# CleverBoard_V1.net
KiCad netlist of a schematic drawn in EAGLE
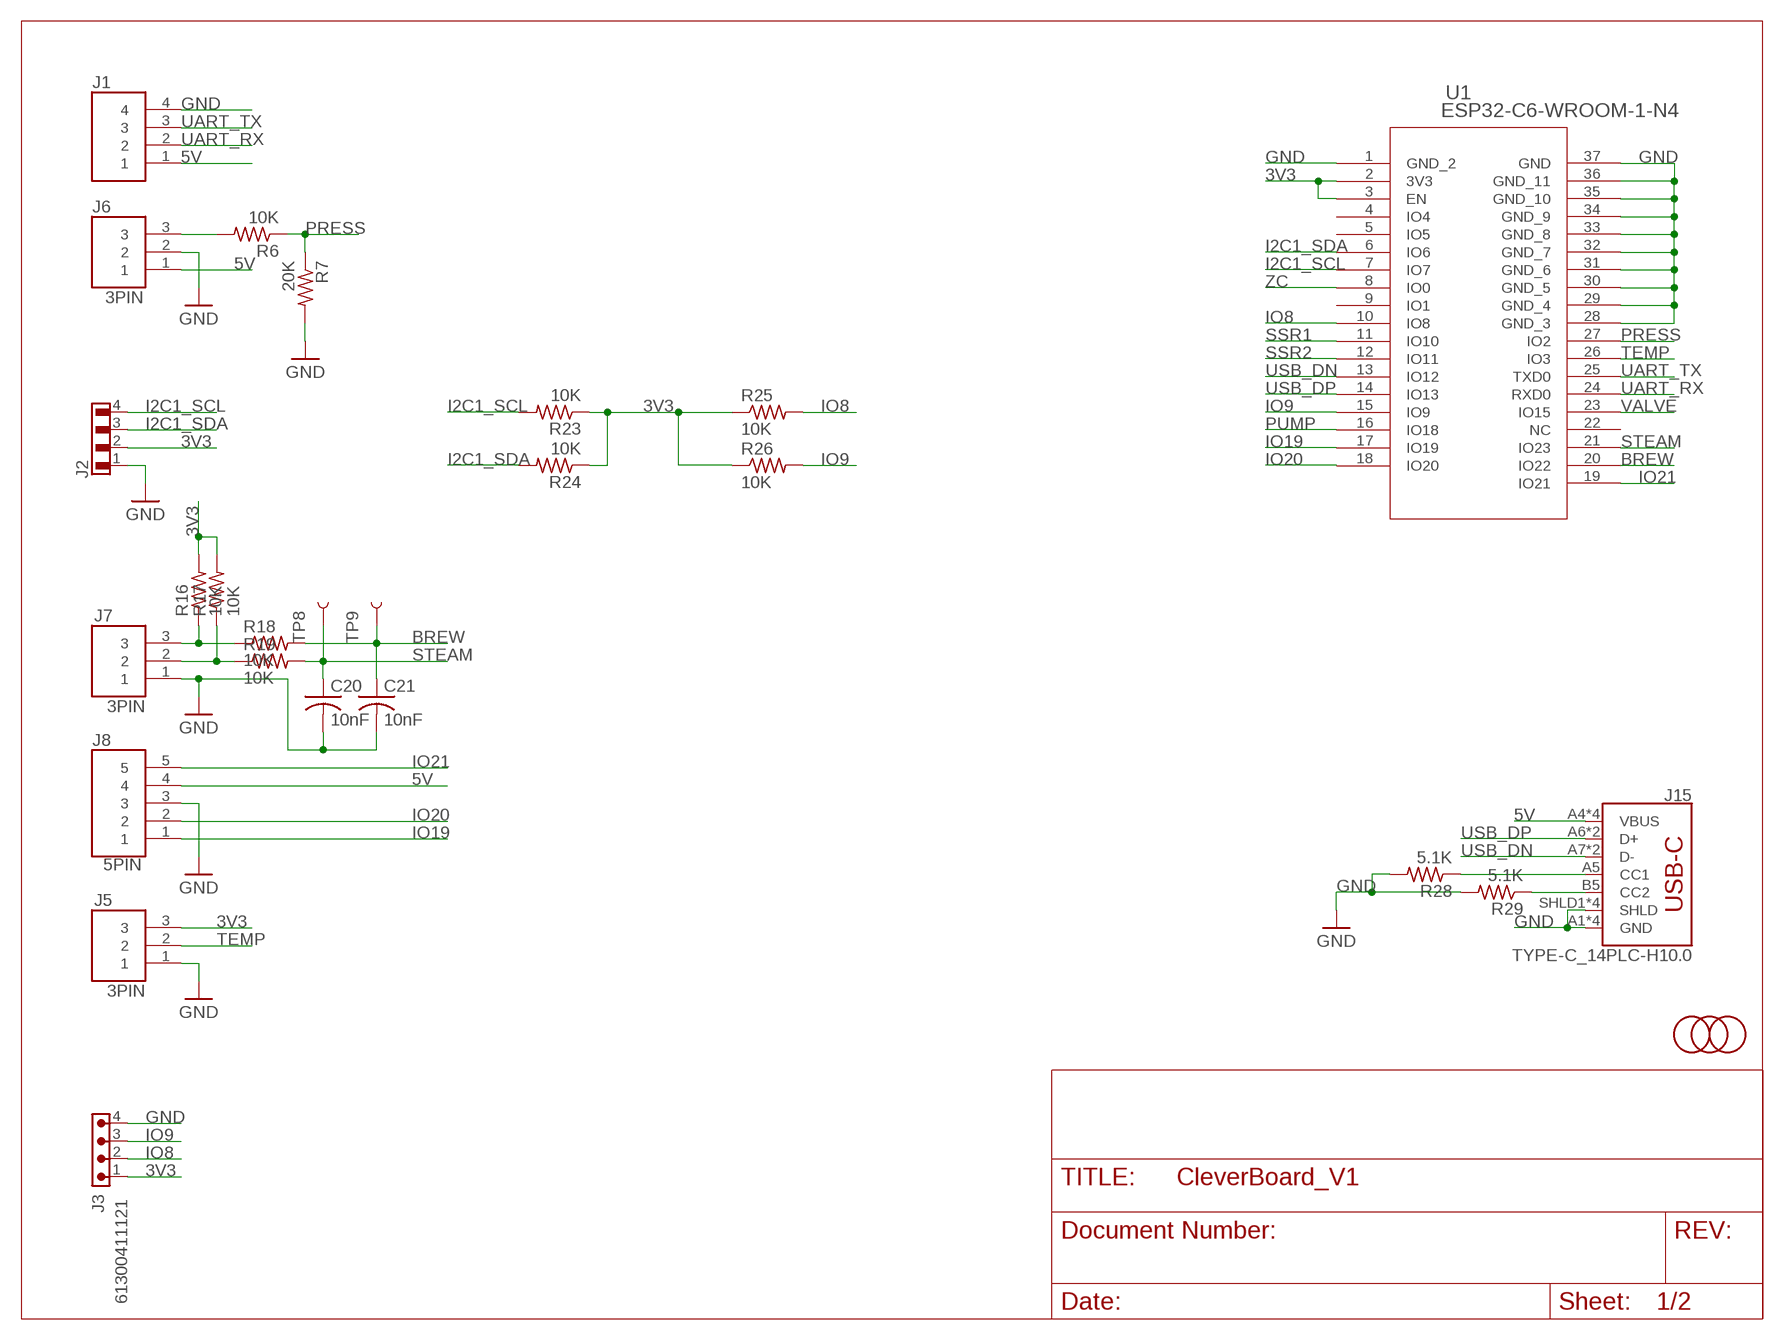
[diagram p0: schematic, sheet 1]
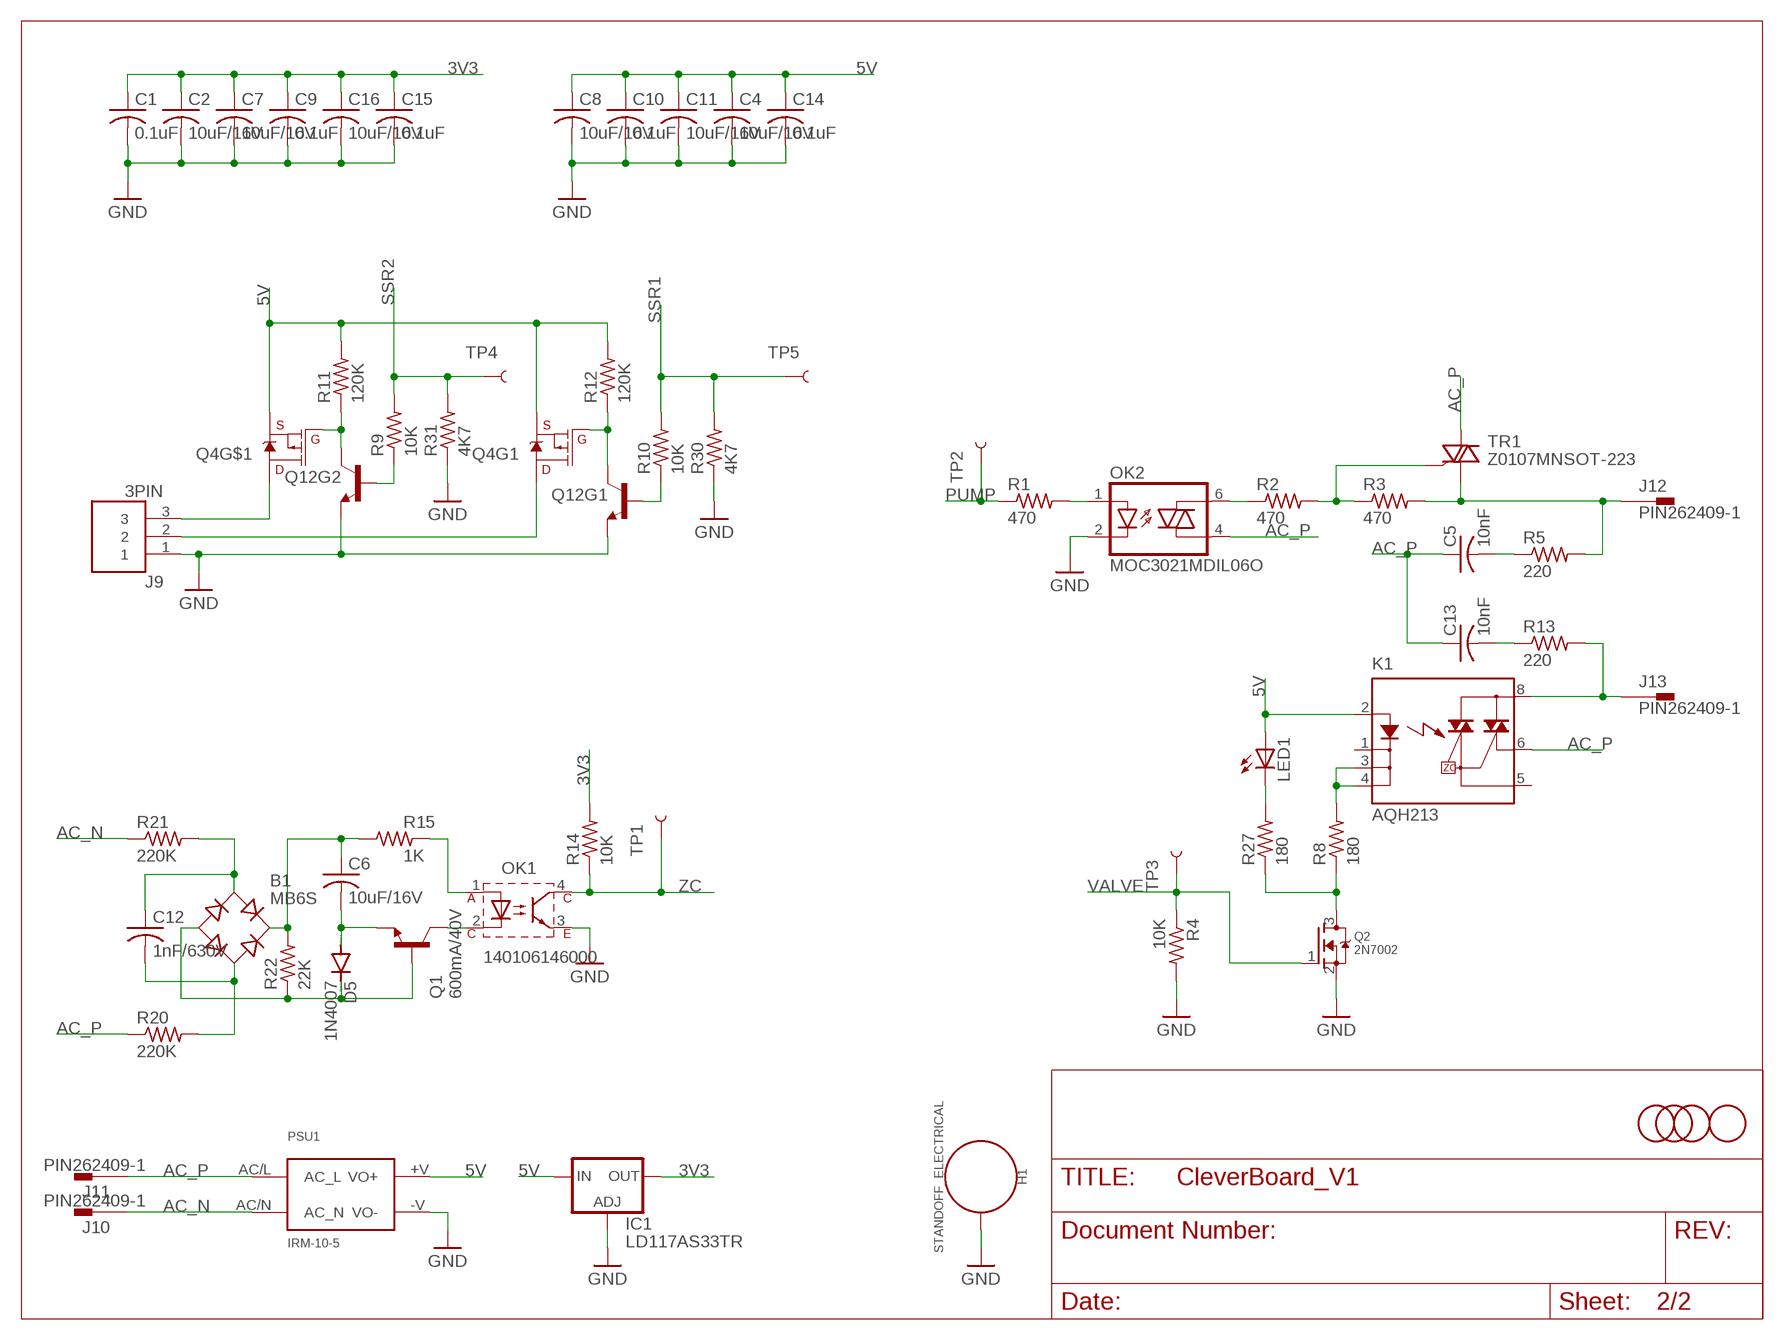
[diagram p1: schematic, sheet 2]

(export (version "E")
  (design (tool "Eeschema 10.0.6"))
  (components
    (comp (ref "C20")
      (value "10nF")
      (footprint "eagle-import:C0603")
      (libsource (lib "eagle-import") (part "C-USC0603"))
    )
    (comp (ref "C21")
      (value "10nF")
      (footprint "eagle-import:C0603")
      (libsource (lib "eagle-import") (part "C-USC0603"))
    )
    (comp (ref "J1")
      (value "4PIN")
      (footprint "eagle-import:B4B-PH-K-S")
      (libsource (lib "eagle-import") (part "4PIN"))
    )
    (comp (ref "J2")
      (value "665104131822")
      (footprint "eagle-import:665104131822")
      (libsource (lib "eagle-import") (part "665104131822"))
    )
    (comp (ref "J3")
      (value "61300411121")
      (footprint "eagle-import:61300411121")
      (libsource (lib "eagle-import") (part "6130XX11121_61300411121"))
    )
    (comp (ref "J5")
      (value "3PIN")
      (footprint "eagle-import:B3B-PH-K-S")
      (libsource (lib "eagle-import") (part "3PIN"))
    )
    (comp (ref "J6")
      (value "3PIN")
      (footprint "eagle-import:B3B-PH-K-S")
      (libsource (lib "eagle-import") (part "3PIN"))
    )
    (comp (ref "J7")
      (value "3PIN")
      (footprint "eagle-import:B3B-PH-K-S")
      (libsource (lib "eagle-import") (part "3PIN"))
    )
    (comp (ref "J8")
      (value "5PIN")
      (footprint "eagle-import:B5B-PH-K-S")
      (libsource (lib "eagle-import") (part "5PIN"))
    )
    (comp (ref "J15")
      (value "TYPE-C_14PLC-H10.0")
      (footprint "eagle-import:TYPE-C_14PLC-H10.0")
      (libsource (lib "eagle-import") (part "TYPE-C_14PLC-H10.0"))
    )
    (comp (ref "MARK1")
      (value "FIDUCIAL")
      (footprint "eagle-import:FIDUCIAL_1MM")
      (libsource (lib "eagle-import") (part "FIDUCIAL"))
    )
    (comp (ref "MARK2")
      (value "FIDUCIAL")
      (footprint "eagle-import:FIDUCIAL_1MM")
      (libsource (lib "eagle-import") (part "FIDUCIAL"))
    )
    (comp (ref "MARK5")
      (value "FIDUCIAL")
      (footprint "eagle-import:FIDUCIAL_1MM")
      (libsource (lib "eagle-import") (part "FIDUCIAL"))
    )
    (comp (ref "R6")
      (value "10K")
      (footprint "eagle-import:R0603")
      (libsource (lib "eagle-import") (part "R-US_R0603"))
    )
    (comp (ref "R7")
      (value "20K")
      (footprint "eagle-import:R0603")
      (libsource (lib "eagle-import") (part "R-US_R0603"))
    )
    (comp (ref "R16")
      (value "10K")
      (footprint "eagle-import:R0603")
      (libsource (lib "eagle-import") (part "R-US_R0603"))
    )
    (comp (ref "R17")
      (value "10K")
      (footprint "eagle-import:R0603")
      (libsource (lib "eagle-import") (part "R-US_R0603"))
    )
    (comp (ref "R18")
      (value "10K")
      (footprint "eagle-import:R0603")
      (libsource (lib "eagle-import") (part "R-US_R0603"))
    )
    (comp (ref "R19")
      (value "10K")
      (footprint "eagle-import:R0603")
      (libsource (lib "eagle-import") (part "R-US_R0603"))
    )
    (comp (ref "R23")
      (value "10K")
      (footprint "eagle-import:R0603")
      (libsource (lib "eagle-import") (part "R-US_R0603"))
    )
    (comp (ref "R24")
      (value "10K")
      (footprint "eagle-import:R0603")
      (libsource (lib "eagle-import") (part "R-US_R0603"))
    )
    (comp (ref "R25")
      (value "10K")
      (footprint "eagle-import:R0603")
      (libsource (lib "eagle-import") (part "R-US_R0603"))
    )
    (comp (ref "R26")
      (value "10K")
      (footprint "eagle-import:R0603")
      (libsource (lib "eagle-import") (part "R-US_R0603"))
    )
    (comp (ref "R28")
      (value "5.1K")
      (footprint "eagle-import:R0603")
      (libsource (lib "eagle-import") (part "R-US_R0603"))
    )
    (comp (ref "R29")
      (value "5.1K")
      (footprint "eagle-import:R0603")
      (libsource (lib "eagle-import") (part "R-US_R0603"))
    )
    (comp (ref "TP8")
      (value "TEST-POINT3")
      (footprint "eagle-import:PAD.03X.03")
      (libsource (lib "eagle-import") (part "TEST-POINT3"))
    )
    (comp (ref "TP9")
      (value "TEST-POINT3")
      (footprint "eagle-import:PAD.03X.03")
      (libsource (lib "eagle-import") (part "TEST-POINT3"))
    )
    (comp (ref "U1")
      (value "ESP32-C6-WROOM-1-N4")
      (footprint "eagle-import:MOD28_ESP32-C6-WROOM-1_EXP")
      (fields (field (name "COPYRIGHT") "Copyright (C) 2025 Ultra Librarian. All rights reserved."))
      (libsource (lib "eagle-import") (part "ESP32-C6-WROOM-1-N4"))
    )
    (comp (ref "B1")
      (value "MB6S")
      (footprint "eagle-import:SOIC-4")
      (libsource (lib "eagle-import") (part "MBS6"))
    )
    (comp (ref "C1")
      (value "0.1uF")
      (footprint "eagle-import:C0603")
      (libsource (lib "eagle-import") (part "C-USC0603"))
    )
    (comp (ref "C2")
      (value "10uF/16V")
      (footprint "eagle-import:C0603")
      (libsource (lib "eagle-import") (part "C-USC0603"))
    )
    (comp (ref "C4")
      (value "10uF/16V")
      (footprint "eagle-import:C0603")
      (libsource (lib "eagle-import") (part "C-USC0603"))
    )
    (comp (ref "C5")
      (value "10nF")
      (footprint "eagle-import:C1206")
      (libsource (lib "eagle-import") (part "C-USC1206"))
    )
    (comp (ref "C6")
      (value "10uF/16V")
      (footprint "eagle-import:C0603")
      (libsource (lib "eagle-import") (part "C-USC0603"))
    )
    (comp (ref "C7")
      (value "10uF/16V")
      (footprint "eagle-import:C0603")
      (libsource (lib "eagle-import") (part "C-USC0603"))
    )
    (comp (ref "C8")
      (value "10uF/16V")
      (footprint "eagle-import:C0603")
      (libsource (lib "eagle-import") (part "C-USC0603"))
    )
    (comp (ref "C9")
      (value "0.1uF")
      (footprint "eagle-import:C0603")
      (libsource (lib "eagle-import") (part "C-USC0603"))
    )
    (comp (ref "C10")
      (value "0.1uF")
      (footprint "eagle-import:C0603")
      (libsource (lib "eagle-import") (part "C-USC0603"))
    )
    (comp (ref "C11")
      (value "10uF/16V")
      (footprint "eagle-import:C0603")
      (libsource (lib "eagle-import") (part "C-USC0603"))
    )
    (comp (ref "C12")
      (value "1nF/630V")
      (footprint "eagle-import:C0805")
      (libsource (lib "eagle-import") (part "C-USC0805"))
    )
    (comp (ref "C13")
      (value "10nF")
      (footprint "eagle-import:C1206")
      (libsource (lib "eagle-import") (part "C-USC1206"))
    )
    (comp (ref "C14")
      (value "0.1uF")
      (footprint "eagle-import:C0603")
      (libsource (lib "eagle-import") (part "C-USC0603"))
    )
    (comp (ref "C15")
      (value "0.1uF")
      (footprint "eagle-import:C0603")
      (libsource (lib "eagle-import") (part "C-USC0603"))
    )
    (comp (ref "C16")
      (value "10uF/16V")
      (footprint "eagle-import:C0603")
      (libsource (lib "eagle-import") (part "C-USC0603"))
    )
    (comp (ref "D5")
      (value "1N4007")
      (footprint "eagle-import:DO214AC")
      (libsource (lib "eagle-import") (part "DIODE-DO214AC"))
    )
    (comp (ref "H1")
      (value "STANDOFF_ELECTRICAL")
      (footprint "eagle-import:STANDOFF-ELECTRICAL")
      (libsource (lib "eagle-import") (part "STANDOFF_ELECTRICAL"))
    )
    (comp (ref "IC1")
      (value "LD117AS33TR")
      (footprint "eagle-import:SOT223")
      (libsource (lib "eagle-import") (part "LD117A?S33TR"))
    )
    (comp (ref "J9")
      (value "3PIN")
      (footprint "eagle-import:B3B-PH-K-S")
      (libsource (lib "eagle-import") (part "3PIN"))
    )
    (comp (ref "J10")
      (value "PIN262409-1")
      (footprint "eagle-import:62409-1")
      (libsource (lib "eagle-import") (part "PIN262409-1"))
    )
    (comp (ref "J11")
      (value "PIN262409-1")
      (footprint "eagle-import:62409-1")
      (libsource (lib "eagle-import") (part "PIN262409-1"))
    )
    (comp (ref "J12")
      (value "PIN262409-1")
      (footprint "eagle-import:62409-1")
      (libsource (lib "eagle-import") (part "PIN262409-1"))
    )
    (comp (ref "J13")
      (value "PIN262409-1")
      (footprint "eagle-import:62409-1")
      (libsource (lib "eagle-import") (part "PIN262409-1"))
    )
    (comp (ref "K1")
      (value "AQH213")
      (footprint "eagle-import:DIL07")
      (libsource (lib "eagle-import") (part "AQH213"))
    )
    (comp (ref "LED1")
      (value "LEDCHIP-LED0603")
      (footprint "eagle-import:CHIP-LED0603")
      (libsource (lib "eagle-import") (part "LEDCHIP-LED0603"))
    )
    (comp (ref "MARK4")
      (value "FIDUCIAL")
      (footprint "eagle-import:FIDUCIAL_1MM")
      (libsource (lib "eagle-import") (part "FIDUCIAL"))
    )
    (comp (ref "MARK6")
      (value "FIDUCIAL")
      (footprint "eagle-import:FIDUCIAL_1MM")
      (libsource (lib "eagle-import") (part "FIDUCIAL"))
    )
    (comp (ref "MARK7")
      (value "FIDUCIAL")
      (footprint "eagle-import:FIDUCIAL_1MM")
      (libsource (lib "eagle-import") (part "FIDUCIAL"))
    )
    (comp (ref "MARK8")
      (value "FIDUCIAL")
      (footprint "eagle-import:FIDUCIAL_1MM")
      (libsource (lib "eagle-import") (part "FIDUCIAL"))
    )
    (comp (ref "OK1")
      (value "140106146000")
      (footprint "eagle-import:WL-OCPT_LSOP4")
      (libsource (lib "eagle-import") (part "WL-OCPT_SERIES_101X_140106146000"))
    )
    (comp (ref "OK2")
      (value "MOC3021MDIL06O")
      (footprint "eagle-import:DIL06O")
      (libsource (lib "eagle-import") (part "MOC3021MDIL06O"))
    )
    (comp (ref "PSU1")
      (value "IRM-10-5")
      (footprint "eagle-import:IRM-10")
      (fields (field (name "SPICEPREFIX") "E"))
      (libsource (lib "eagle-import") (part "IRM-10-5"))
    )
    (comp (ref "Q1")
      (value "600mA/40V")
      (footprint "eagle-import:SOT23-3")
      (libsource (lib "eagle-import") (part "TRANS_NPN-MMBT2222AL"))
    )
    (comp (ref "Q2")
      (value "2N7002")
      (footprint "eagle-import:SOT23-R")
      (libsource (lib "eagle-import") (part "MOSFET-NREFLOW"))
    )
    (comp (ref "Q4")
      (value "MOSFET_PCH_DUAL-DMP2240UDM")
      (footprint "eagle-import:SOT26")
      (fields (field (name "LCSC") "C397948"))
      (libsource (lib "eagle-import") (part "MOSFET_PCH_DUAL-DMP2240UDM"))
    )
    (comp (ref "Q12")
      (value "TRANS_NPN_DUAL-MBT3904DW1T1")
      (footprint "eagle-import:SC70-6")
      (fields (field (name "LCSC") "C896759"))
      (libsource (lib "eagle-import") (part "TRANS_NPN_DUAL-MBT3904DW1T1"))
    )
    (comp (ref "R1")
      (value "470")
      (footprint "eagle-import:R0603")
      (libsource (lib "eagle-import") (part "R-US_R0603"))
    )
    (comp (ref "R2")
      (value "470")
      (footprint "eagle-import:R0603")
      (libsource (lib "eagle-import") (part "R-US_R0603"))
    )
    (comp (ref "R3")
      (value "470")
      (footprint "eagle-import:R0603")
      (libsource (lib "eagle-import") (part "R-US_R0603"))
    )
    (comp (ref "R4")
      (value "10K")
      (footprint "eagle-import:R0603")
      (libsource (lib "eagle-import") (part "R-US_R0603"))
    )
    (comp (ref "R5")
      (value "220")
      (footprint "eagle-import:R2512")
      (libsource (lib "eagle-import") (part "R-US_R2512"))
    )
    (comp (ref "R8")
      (value "180")
      (footprint "eagle-import:R0603")
      (libsource (lib "eagle-import") (part "R-US_R0603"))
    )
    (comp (ref "R9")
      (value "10K")
      (footprint "eagle-import:R0603")
      (libsource (lib "eagle-import") (part "R-US_R0603"))
    )
    (comp (ref "R10")
      (value "10K")
      (footprint "eagle-import:R0603")
      (libsource (lib "eagle-import") (part "R-US_R0603"))
    )
    (comp (ref "R11")
      (value "120K")
      (footprint "eagle-import:R0603")
      (libsource (lib "eagle-import") (part "R-US_R0603"))
    )
    (comp (ref "R12")
      (value "120K")
      (footprint "eagle-import:R0603")
      (libsource (lib "eagle-import") (part "R-US_R0603"))
    )
    (comp (ref "R13")
      (value "220")
      (footprint "eagle-import:R2512")
      (libsource (lib "eagle-import") (part "R-US_R2512"))
    )
    (comp (ref "R14")
      (value "10K")
      (footprint "eagle-import:R0603")
      (libsource (lib "eagle-import") (part "R-US_R0603"))
    )
    (comp (ref "R15")
      (value "1K")
      (footprint "eagle-import:R0603")
      (libsource (lib "eagle-import") (part "R-US_R0603"))
    )
    (comp (ref "R20")
      (value "220K")
      (footprint "eagle-import:R1206")
      (libsource (lib "eagle-import") (part "R-US_R1206"))
    )
    (comp (ref "R21")
      (value "220K")
      (footprint "eagle-import:R1206")
      (libsource (lib "eagle-import") (part "R-US_R1206"))
    )
    (comp (ref "R22")
      (value "22K")
      (footprint "eagle-import:R0603")
      (libsource (lib "eagle-import") (part "R-US_R0603"))
    )
    (comp (ref "R27")
      (value "180")
      (footprint "eagle-import:R0603")
      (libsource (lib "eagle-import") (part "R-US_R0603"))
    )
    (comp (ref "R30")
      (value "4K7")
      (footprint "eagle-import:R0603")
      (libsource (lib "eagle-import") (part "R-US_R0603"))
    )
    (comp (ref "R31")
      (value "4K7")
      (footprint "eagle-import:R0603")
      (libsource (lib "eagle-import") (part "R-US_R0603"))
    )
    (comp (ref "TP1")
      (value "TEST-POINT3")
      (footprint "eagle-import:PAD.03X.03")
      (libsource (lib "eagle-import") (part "TEST-POINT3"))
    )
    (comp (ref "TP2")
      (value "TEST-POINT3")
      (footprint "eagle-import:PAD.03X.03")
      (libsource (lib "eagle-import") (part "TEST-POINT3"))
    )
    (comp (ref "TP3")
      (value "TEST-POINT3")
      (footprint "eagle-import:PAD.03X.03")
      (libsource (lib "eagle-import") (part "TEST-POINT3"))
    )
    (comp (ref "TP4")
      (value "TEST-POINT3")
      (footprint "eagle-import:PAD.03X.03")
      (libsource (lib "eagle-import") (part "TEST-POINT3"))
    )
    (comp (ref "TP5")
      (value "TEST-POINT3")
      (footprint "eagle-import:PAD.03X.03")
      (libsource (lib "eagle-import") (part "TEST-POINT3"))
    )
    (comp (ref "TR1")
      (value "Z0107MNSOT-223")
      (footprint "eagle-import:SOT223")
      (libsource (lib "eagle-import") (part "Z0107MNSOT-223"))
    )
  )
  (nets
    (net (code "1") (name "3V3") (class "Default")
      (node (ref "C1") (pin "1") (pinfunction "1_1") (pintype "passive"))
      (node (ref "C15") (pin "1") (pinfunction "1_1") (pintype "passive"))
      (node (ref "C16") (pin "1") (pinfunction "1_1") (pintype "passive"))
      (node (ref "C2") (pin "1") (pinfunction "1_1") (pintype "passive"))
      (node (ref "C7") (pin "1") (pinfunction "1_1") (pintype "passive"))
      (node (ref "C9") (pin "1") (pinfunction "1_1") (pintype "passive"))
      (node (ref "IC1") (pin "4") (pinfunction "OUT_4") (pintype "passive"))
      (node (ref "J2") (pin "2") (pinfunction "2_2") (pintype "passive"))
      (node (ref "J3") (pin "1") (pinfunction "1_1") (pintype "passive"))
      (node (ref "J5") (pin "3") (pinfunction "3_3") (pintype "bidirectional"))
      (node (ref "R14") (pin "2") (pinfunction "2_2") (pintype "passive"))
      (node (ref "R16") (pin "2") (pinfunction "2_2") (pintype "passive"))
      (node (ref "R17") (pin "2") (pinfunction "2_2") (pintype "passive"))
      (node (ref "R23") (pin "1") (pinfunction "1_1") (pintype "passive"))
      (node (ref "R24") (pin "1") (pinfunction "1_1") (pintype "passive"))
      (node (ref "R25") (pin "1") (pinfunction "1_1") (pintype "passive"))
      (node (ref "R26") (pin "1") (pinfunction "1_1") (pintype "passive"))
      (node (ref "U1") (pin "2") (pinfunction "3V3_2") (pintype "power_in"))
      (node (ref "U1") (pin "3") (pinfunction "EN_3") (pintype "input"))
    )
    (net (code "2") (name "5V") (class "Default")
      (node (ref "C10") (pin "1") (pinfunction "1_1") (pintype "passive"))
      (node (ref "C11") (pin "1") (pinfunction "1_1") (pintype "passive"))
      (node (ref "C14") (pin "1") (pinfunction "1_1") (pintype "passive"))
      (node (ref "C4") (pin "1") (pinfunction "1_1") (pintype "passive"))
      (node (ref "C8") (pin "1") (pinfunction "1_1") (pintype "passive"))
      (node (ref "IC1") (pin "3") (pinfunction "IN_3") (pintype "input"))
      (node (ref "J1") (pin "1") (pinfunction "1_1") (pintype "bidirectional"))
      (node (ref "J15") (pin "A4") (pinfunction "VBUS_A4") (pintype "bidirectional"))
      (node (ref "J15") (pin "A9") (pinfunction "VBUS_A9") (pintype "bidirectional"))
      (node (ref "J15") (pin "B4") (pinfunction "VBUS_B4") (pintype "bidirectional"))
      (node (ref "J15") (pin "B9") (pinfunction "VBUS_B9") (pintype "bidirectional"))
      (node (ref "J6") (pin "1") (pinfunction "1_1") (pintype "bidirectional"))
      (node (ref "J8") (pin "4") (pinfunction "4_4") (pintype "bidirectional"))
      (node (ref "K1") (pin "2") (pinfunction "A_2") (pintype "passive"))
      (node (ref "LED1") (pin "A") (pinfunction "A_A") (pintype "passive"))
      (node (ref "PSU1") (pin "+V") (pinfunction "VO+_+V") (pintype "bidirectional"))
      (node (ref "Q4") (pin "S1") (pinfunction "S_S1") (pintype "bidirectional"))
      (node (ref "Q4") (pin "S2") (pinfunction "S_S2") (pintype "bidirectional"))
      (node (ref "R11") (pin "2") (pinfunction "2_2") (pintype "passive"))
      (node (ref "R12") (pin "2") (pinfunction "2_2") (pintype "passive"))
    )
    (net (code "3") (name "AC_N") (class "Default")
      (node (ref "J10") (pin "A1") (pinfunction "1_A1") (pintype "passive"))
      (node (ref "J10") (pin "A2") (pinfunction "1_A2") (pintype "passive"))
      (node (ref "PSU1") (pin "AC/N") (pinfunction "AC_N_AC/N") (pintype "bidirectional"))
      (node (ref "R21") (pin "1") (pinfunction "1_1") (pintype "passive"))
    )
    (net (code "4") (name "AC_P") (class "Default")
      (node (ref "C13") (pin "1") (pinfunction "1_1") (pintype "passive"))
      (node (ref "C5") (pin "1") (pinfunction "1_1") (pintype "passive"))
      (node (ref "J11") (pin "A1") (pinfunction "1_A1") (pintype "passive"))
      (node (ref "J11") (pin "A2") (pinfunction "1_A2") (pintype "passive"))
      (node (ref "K1") (pin "6") (pinfunction "DS3_6") (pintype "passive"))
      (node (ref "OK2") (pin "4") (pinfunction "A1_4") (pintype "passive"))
      (node (ref "PSU1") (pin "AC/L") (pinfunction "AC_L_AC/L") (pintype "bidirectional"))
      (node (ref "R20") (pin "1") (pinfunction "1_1") (pintype "passive"))
      (node (ref "TR1") (pin "2") (pinfunction "A2_2") (pintype "passive"))
      (node (ref "TR1") (pin "4") (pinfunction "A2_4") (pintype "passive"))
    )
    (net (code "5") (name "BREW") (class "Default")
      (node (ref "C21") (pin "1") (pinfunction "1_1") (pintype "passive"))
      (node (ref "R18") (pin "2") (pinfunction "2_2") (pintype "passive"))
      (node (ref "TP9") (pin "1") (pinfunction "1_1") (pintype "bidirectional"))
      (node (ref "U1") (pin "20") (pinfunction "IO22_20") (pintype "bidirectional"))
    )
    (net (code "6") (name "GND") (class "Default")
      (node (ref "C1") (pin "2") (pinfunction "2_2") (pintype "passive"))
      (node (ref "C10") (pin "2") (pinfunction "2_2") (pintype "passive"))
      (node (ref "C11") (pin "2") (pinfunction "2_2") (pintype "passive"))
      (node (ref "C14") (pin "2") (pinfunction "2_2") (pintype "passive"))
      (node (ref "C15") (pin "2") (pinfunction "2_2") (pintype "passive"))
      (node (ref "C16") (pin "2") (pinfunction "2_2") (pintype "passive"))
      (node (ref "C2") (pin "2") (pinfunction "2_2") (pintype "passive"))
      (node (ref "C20") (pin "2") (pinfunction "2_2") (pintype "passive"))
      (node (ref "C21") (pin "2") (pinfunction "2_2") (pintype "passive"))
      (node (ref "C4") (pin "2") (pinfunction "2_2") (pintype "passive"))
      (node (ref "C7") (pin "2") (pinfunction "2_2") (pintype "passive"))
      (node (ref "C8") (pin "2") (pinfunction "2_2") (pintype "passive"))
      (node (ref "C9") (pin "2") (pinfunction "2_2") (pintype "passive"))
      (node (ref "H1") (pin "P1") (pinfunction "P$1_P1") (pintype "bidirectional"))
      (node (ref "IC1") (pin "1") (pinfunction "ADJ_1") (pintype "input"))
      (node (ref "J1") (pin "4") (pinfunction "4_4") (pintype "bidirectional"))
      (node (ref "J15") (pin "A1") (pinfunction "GND_A1") (pintype "bidirectional"))
      (node (ref "J15") (pin "A12") (pinfunction "GND_A12") (pintype "bidirectional"))
      (node (ref "J15") (pin "B1") (pinfunction "GND_B1") (pintype "bidirectional"))
      (node (ref "J15") (pin "B12") (pinfunction "GND_B12") (pintype "bidirectional"))
      (node (ref "J15") (pin "SHLD1") (pinfunction "SHLD_SHLD1") (pintype "bidirectional"))
      (node (ref "J15") (pin "SHLD2") (pinfunction "SHLD_SHLD2") (pintype "bidirectional"))
      (node (ref "J15") (pin "SHLD3") (pinfunction "SHLD_SHLD3") (pintype "bidirectional"))
      (node (ref "J15") (pin "SHLD4") (pinfunction "SHLD_SHLD4") (pintype "bidirectional"))
      (node (ref "J2") (pin "1") (pinfunction "1_1") (pintype "passive"))
      (node (ref "J3") (pin "4") (pinfunction "4_4") (pintype "passive"))
      (node (ref "J5") (pin "1") (pinfunction "1_1") (pintype "bidirectional"))
      (node (ref "J6") (pin "2") (pinfunction "2_2") (pintype "bidirectional"))
      (node (ref "J7") (pin "1") (pinfunction "1_1") (pintype "bidirectional"))
      (node (ref "J8") (pin "3") (pinfunction "3_3") (pintype "bidirectional"))
      (node (ref "J9") (pin "1") (pinfunction "1_1") (pintype "bidirectional"))
      (node (ref "OK1") (pin "3") (pinfunction "3_3") (pintype "passive"))
      (node (ref "OK2") (pin "2") (pinfunction "C_2") (pintype "passive"))
      (node (ref "PSU1") (pin "-V") (pinfunction "VO-_-V") (pintype "bidirectional"))
      (node (ref "Q12") (pin "1") (pinfunction "E_1") (pintype "passive"))
      (node (ref "Q12") (pin "4") (pinfunction "E_4") (pintype "passive"))
      (node (ref "Q2") (pin "2") (pinfunction "S_2") (pintype "bidirectional"))
      (node (ref "R28") (pin "2") (pinfunction "2_2") (pintype "passive"))
      (node (ref "R29") (pin "2") (pinfunction "2_2") (pintype "passive"))
      (node (ref "R30") (pin "1") (pinfunction "1_1") (pintype "passive"))
      (node (ref "R31") (pin "1") (pinfunction "1_1") (pintype "passive"))
      (node (ref "R4") (pin "2") (pinfunction "2_2") (pintype "passive"))
      (node (ref "R7") (pin "2") (pinfunction "2_2") (pintype "passive"))
      (node (ref "U1") (pin "1") (pinfunction "GND_2_1") (pintype "passive"))
      (node (ref "U1") (pin "28") (pinfunction "GND_3_28") (pintype "passive"))
      (node (ref "U1") (pin "29") (pinfunction "GND_4_29") (pintype "passive"))
      (node (ref "U1") (pin "30") (pinfunction "GND_5_30") (pintype "passive"))
      (node (ref "U1") (pin "31") (pinfunction "GND_6_31") (pintype "passive"))
      (node (ref "U1") (pin "32") (pinfunction "GND_7_32") (pintype "passive"))
      (node (ref "U1") (pin "33") (pinfunction "GND_8_33") (pintype "passive"))
      (node (ref "U1") (pin "34") (pinfunction "GND_9_34") (pintype "passive"))
      (node (ref "U1") (pin "35") (pinfunction "GND_10_35") (pintype "passive"))
      (node (ref "U1") (pin "36") (pinfunction "GND_11_36") (pintype "passive"))
      (node (ref "U1") (pin "37") (pinfunction "GND_37") (pintype "passive"))
    )
    (net (code "7") (name "I2C1_SCL") (class "Default")
      (node (ref "J2") (pin "4") (pinfunction "4_4") (pintype "passive"))
      (node (ref "R23") (pin "2") (pinfunction "2_2") (pintype "passive"))
      (node (ref "U1") (pin "7") (pinfunction "IO7_7") (pintype "bidirectional"))
    )
    (net (code "8") (name "I2C1_SDA") (class "Default")
      (node (ref "J2") (pin "3") (pinfunction "3_3") (pintype "passive"))
      (node (ref "R24") (pin "2") (pinfunction "2_2") (pintype "passive"))
      (node (ref "U1") (pin "6") (pinfunction "IO6_6") (pintype "bidirectional"))
    )
    (net (code "9") (name "IO8") (class "Default")
      (node (ref "J3") (pin "2") (pinfunction "2_2") (pintype "passive"))
      (node (ref "R25") (pin "2") (pinfunction "2_2") (pintype "passive"))
      (node (ref "U1") (pin "10") (pinfunction "IO8_10") (pintype "bidirectional"))
    )
    (net (code "10") (name "IO9") (class "Default")
      (node (ref "J3") (pin "3") (pinfunction "3_3") (pintype "passive"))
      (node (ref "R26") (pin "2") (pinfunction "2_2") (pintype "passive"))
      (node (ref "U1") (pin "15") (pinfunction "IO9_15") (pintype "bidirectional"))
    )
    (net (code "11") (name "IO19") (class "Default")
      (node (ref "J8") (pin "1") (pinfunction "1_1") (pintype "bidirectional"))
      (node (ref "U1") (pin "17") (pinfunction "IO19_17") (pintype "bidirectional"))
    )
    (net (code "12") (name "IO20") (class "Default")
      (node (ref "J8") (pin "2") (pinfunction "2_2") (pintype "bidirectional"))
      (node (ref "U1") (pin "18") (pinfunction "IO20_18") (pintype "bidirectional"))
    )
    (net (code "13") (name "IO21") (class "Default")
      (node (ref "J8") (pin "5") (pinfunction "5_5") (pintype "bidirectional"))
      (node (ref "U1") (pin "19") (pinfunction "IO21_19") (pintype "bidirectional"))
    )
    (net (code "14") (name "Net-(B1-AC1)") (class "Default")
      (node (ref "B1") (pin "~1") (pinfunction "AC1_~1") (pintype "passive"))
      (node (ref "C12") (pin "2") (pinfunction "2_2") (pintype "passive"))
      (node (ref "R20") (pin "2") (pinfunction "2_2") (pintype "passive"))
    )
    (net (code "15") (name "Net-(B1-AC2)") (class "Default")
      (node (ref "B1") (pin "~2") (pinfunction "AC2_~2") (pintype "passive"))
      (node (ref "C12") (pin "1") (pinfunction "1_1") (pintype "passive"))
      (node (ref "R21") (pin "2") (pinfunction "2_2") (pintype "passive"))
    )
    (net (code "16") (name "Net-(B1-Pad+)") (class "Default")
      (node (ref "B1") (pin "+") (pinfunction "+_+") (pintype "passive"))
      (node (ref "C6") (pin "1") (pinfunction "1_1") (pintype "passive"))
      (node (ref "R15") (pin "1") (pinfunction "1_1") (pintype "passive"))
      (node (ref "R22") (pin "2") (pinfunction "2_2") (pintype "passive"))
    )
    (net (code "17") (name "Net-(C5-Pad2)") (class "Default")
      (node (ref "C5") (pin "2") (pinfunction "2_2") (pintype "passive"))
      (node (ref "R5") (pin "1") (pinfunction "1_1") (pintype "passive"))
    )
    (net (code "18") (name "Net-(C13-Pad2)") (class "Default")
      (node (ref "C13") (pin "2") (pinfunction "2_2") (pintype "passive"))
      (node (ref "R13") (pin "1") (pinfunction "1_1") (pintype "passive"))
    )
    (net (code "19") (name "Net-(J6-Pad3)") (class "Default")
      (node (ref "J6") (pin "3") (pinfunction "3_3") (pintype "bidirectional"))
      (node (ref "R6") (pin "2") (pinfunction "2_2") (pintype "passive"))
    )
    (net (code "20") (name "Net-(J7-Pad2)") (class "Default")
      (node (ref "J7") (pin "2") (pinfunction "2_2") (pintype "bidirectional"))
      (node (ref "R17") (pin "1") (pinfunction "1_1") (pintype "passive"))
      (node (ref "R19") (pin "1") (pinfunction "1_1") (pintype "passive"))
    )
    (net (code "21") (name "Net-(J7-Pad3)") (class "Default")
      (node (ref "J7") (pin "3") (pinfunction "3_3") (pintype "bidirectional"))
      (node (ref "R16") (pin "1") (pinfunction "1_1") (pintype "passive"))
      (node (ref "R18") (pin "1") (pinfunction "1_1") (pintype "passive"))
    )
    (net (code "22") (name "Net-(J15-CC1)") (class "Default")
      (node (ref "J15") (pin "A5") (pinfunction "CC1_A5") (pintype "bidirectional"))
      (node (ref "R28") (pin "1") (pinfunction "1_1") (pintype "passive"))
    )
    (net (code "23") (name "Net-(J15-CC2)") (class "Default")
      (node (ref "J15") (pin "B5") (pinfunction "CC2_B5") (pintype "bidirectional"))
      (node (ref "R29") (pin "1") (pinfunction "1_1") (pintype "passive"))
    )
    (net (code "24") (name "Net-(K1-DS1)") (class "Default")
      (node (ref "J13") (pin "A1") (pinfunction "1_A1") (pintype "passive"))
      (node (ref "J13") (pin "A2") (pinfunction "1_A2") (pintype "passive"))
      (node (ref "K1") (pin "8") (pinfunction "DS1_8") (pintype "passive"))
      (node (ref "R13") (pin "2") (pinfunction "2_2") (pintype "passive"))
    )
    (net (code "25") (name "Net-(K1-K1)") (class "Default")
      (node (ref "K1") (pin "3") (pinfunction "K1_3") (pintype "passive"))
      (node (ref "K1") (pin "4") (pinfunction "K2_4") (pintype "passive"))
      (node (ref "R8") (pin "2") (pinfunction "2_2") (pintype "passive"))
    )
    (net (code "26") (name "Net-(LED1-PadC)") (class "Default")
      (node (ref "LED1") (pin "C") (pinfunction "C_C") (pintype "passive"))
      (node (ref "R27") (pin "2") (pinfunction "2_2") (pintype "passive"))
    )
    (net (code "27") (name "Net-(OK1-Pad1)") (class "Default")
      (node (ref "OK1") (pin "1") (pinfunction "1_1") (pintype "passive"))
      (node (ref "R15") (pin "2") (pinfunction "2_2") (pintype "passive"))
    )
    (net (code "28") (name "Net-(OK2-A)") (class "Default")
      (node (ref "OK2") (pin "1") (pinfunction "A_1") (pintype "passive"))
      (node (ref "R1") (pin "2") (pinfunction "2_2") (pintype "passive"))
    )
    (net (code "29") (name "Net-(OK2-A2)") (class "Default")
      (node (ref "OK2") (pin "6") (pinfunction "A2_6") (pintype "passive"))
      (node (ref "R2") (pin "1") (pinfunction "1_1") (pintype "passive"))
    )
    (net (code "30") (name "Net-(Q1-B)") (class "Default")
      (node (ref "B1") (pin "-") (pinfunction "-_-") (pintype "passive"))
      (node (ref "D5") (pin "C") (pinfunction "C_C") (pintype "passive"))
      (node (ref "Q1") (pin "1") (pinfunction "B_1") (pintype "passive"))
      (node (ref "R22") (pin "1") (pinfunction "1_1") (pintype "passive"))
    )
    (net (code "31") (name "Net-(Q1-C)") (class "Default")
      (node (ref "OK1") (pin "2") (pinfunction "2_2") (pintype "passive"))
      (node (ref "Q1") (pin "3") (pinfunction "C_3") (pintype "passive"))
    )
    (net (code "32") (name "Net-(Q1-E)") (class "Default")
      (node (ref "C6") (pin "2") (pinfunction "2_2") (pintype "passive"))
      (node (ref "D5") (pin "A") (pinfunction "A_A") (pintype "passive"))
      (node (ref "Q1") (pin "2") (pinfunction "E_2") (pintype "passive"))
    )
    (net (code "33") (name "Net-(Q2-D)") (class "Default")
      (node (ref "Q2") (pin "3") (pinfunction "D_3") (pintype "bidirectional"))
      (node (ref "R27") (pin "1") (pinfunction "1_1") (pintype "passive"))
      (node (ref "R8") (pin "1") (pinfunction "1_1") (pintype "passive"))
    )
    (net (code "34") (name "Net-(Q4A-D)") (class "Default")
      (node (ref "J9") (pin "3") (pinfunction "3_3") (pintype "bidirectional"))
      (node (ref "Q4") (pin "D2") (pinfunction "D_D2") (pintype "bidirectional"))
    )
    (net (code "35") (name "Net-(Q4B-D)") (class "Default")
      (node (ref "J9") (pin "2") (pinfunction "2_2") (pintype "bidirectional"))
      (node (ref "Q4") (pin "D1") (pinfunction "D_D1") (pintype "bidirectional"))
    )
    (net (code "36") (name "Net-(Q12A-B)") (class "Default")
      (node (ref "Q12") (pin "5") (pinfunction "B_5") (pintype "passive"))
      (node (ref "R10") (pin "1") (pinfunction "1_1") (pintype "passive"))
    )
    (net (code "37") (name "Net-(Q12A-C)") (class "Default")
      (node (ref "Q12") (pin "3") (pinfunction "C_3") (pintype "passive"))
      (node (ref "Q4") (pin "G1") (pinfunction "G_G1") (pintype "bidirectional"))
      (node (ref "R12") (pin "1") (pinfunction "1_1") (pintype "passive"))
    )
    (net (code "38") (name "Net-(Q12B-B)") (class "Default")
      (node (ref "Q12") (pin "2") (pinfunction "B_2") (pintype "passive"))
      (node (ref "R9") (pin "1") (pinfunction "1_1") (pintype "passive"))
    )
    (net (code "39") (name "Net-(Q12B-C)") (class "Default")
      (node (ref "Q12") (pin "6") (pinfunction "C_6") (pintype "passive"))
      (node (ref "Q4") (pin "G2") (pinfunction "G_G2") (pintype "bidirectional"))
      (node (ref "R11") (pin "1") (pinfunction "1_1") (pintype "passive"))
    )
    (net (code "40") (name "Net-(TR1-A1)") (class "Default")
      (node (ref "J12") (pin "A1") (pinfunction "1_A1") (pintype "passive"))
      (node (ref "J12") (pin "A2") (pinfunction "1_A2") (pintype "passive"))
      (node (ref "R3") (pin "2") (pinfunction "2_2") (pintype "passive"))
      (node (ref "R5") (pin "2") (pinfunction "2_2") (pintype "passive"))
      (node (ref "TR1") (pin "1") (pinfunction "A1_1") (pintype "passive"))
    )
    (net (code "41") (name "Net-(TR1-G)") (class "Default")
      (node (ref "R2") (pin "2") (pinfunction "2_2") (pintype "passive"))
      (node (ref "R3") (pin "1") (pinfunction "1_1") (pintype "passive"))
      (node (ref "TR1") (pin "3") (pinfunction "G_3") (pintype "passive"))
    )
    (net (code "42") (name "PRESS") (class "Default")
      (node (ref "R6") (pin "1") (pinfunction "1_1") (pintype "passive"))
      (node (ref "R7") (pin "1") (pinfunction "1_1") (pintype "passive"))
      (node (ref "U1") (pin "27") (pinfunction "IO2_27") (pintype "bidirectional"))
    )
    (net (code "43") (name "PUMP") (class "Default")
      (node (ref "R1") (pin "1") (pinfunction "1_1") (pintype "passive"))
      (node (ref "TP2") (pin "1") (pinfunction "1_1") (pintype "bidirectional"))
      (node (ref "U1") (pin "16") (pinfunction "IO18_16") (pintype "bidirectional"))
    )
    (net (code "44") (name "SSR1") (class "Default")
      (node (ref "R10") (pin "2") (pinfunction "2_2") (pintype "passive"))
      (node (ref "R30") (pin "2") (pinfunction "2_2") (pintype "passive"))
      (node (ref "TP5") (pin "1") (pinfunction "1_1") (pintype "bidirectional"))
      (node (ref "U1") (pin "11") (pinfunction "IO10_11") (pintype "bidirectional"))
    )
    (net (code "45") (name "SSR2") (class "Default")
      (node (ref "R31") (pin "2") (pinfunction "2_2") (pintype "passive"))
      (node (ref "R9") (pin "2") (pinfunction "2_2") (pintype "passive"))
      (node (ref "TP4") (pin "1") (pinfunction "1_1") (pintype "bidirectional"))
      (node (ref "U1") (pin "12") (pinfunction "IO11_12") (pintype "bidirectional"))
    )
    (net (code "46") (name "STEAM") (class "Default")
      (node (ref "C20") (pin "1") (pinfunction "1_1") (pintype "passive"))
      (node (ref "R19") (pin "2") (pinfunction "2_2") (pintype "passive"))
      (node (ref "TP8") (pin "1") (pinfunction "1_1") (pintype "bidirectional"))
      (node (ref "U1") (pin "21") (pinfunction "IO23_21") (pintype "bidirectional"))
    )
    (net (code "47") (name "TEMP") (class "Default")
      (node (ref "J5") (pin "2") (pinfunction "2_2") (pintype "bidirectional"))
      (node (ref "U1") (pin "26") (pinfunction "IO3_26") (pintype "bidirectional"))
    )
    (net (code "48") (name "UART_RX") (class "Default")
      (node (ref "J1") (pin "2") (pinfunction "2_2") (pintype "bidirectional"))
      (node (ref "U1") (pin "24") (pinfunction "RXD0_24") (pintype "bidirectional"))
    )
    (net (code "49") (name "UART_TX") (class "Default")
      (node (ref "J1") (pin "3") (pinfunction "3_3") (pintype "bidirectional"))
      (node (ref "U1") (pin "25") (pinfunction "TXD0_25") (pintype "bidirectional"))
    )
    (net (code "50") (name "USB_DN") (class "Default")
      (node (ref "J15") (pin "A7") (pinfunction "D-_A7") (pintype "bidirectional"))
      (node (ref "J15") (pin "B7") (pinfunction "D-_B7") (pintype "bidirectional"))
      (node (ref "U1") (pin "13") (pinfunction "IO12_13") (pintype "bidirectional"))
    )
    (net (code "51") (name "USB_DP") (class "Default")
      (node (ref "J15") (pin "A6") (pinfunction "D+_A6") (pintype "bidirectional"))
      (node (ref "J15") (pin "B6") (pinfunction "D+_B6") (pintype "bidirectional"))
      (node (ref "U1") (pin "14") (pinfunction "IO13_14") (pintype "bidirectional"))
    )
    (net (code "52") (name "VALVE") (class "Default")
      (node (ref "Q2") (pin "1") (pinfunction "G_1") (pintype "bidirectional"))
      (node (ref "R4") (pin "1") (pinfunction "1_1") (pintype "passive"))
      (node (ref "TP3") (pin "1") (pinfunction "1_1") (pintype "bidirectional"))
      (node (ref "U1") (pin "23") (pinfunction "IO15_23") (pintype "bidirectional"))
    )
    (net (code "53") (name "ZC") (class "Default")
      (node (ref "OK1") (pin "4") (pinfunction "4_4") (pintype "passive"))
      (node (ref "R14") (pin "1") (pinfunction "1_1") (pintype "passive"))
      (node (ref "TP1") (pin "1") (pinfunction "1_1") (pintype "bidirectional"))
      (node (ref "U1") (pin "8") (pinfunction "IO0_8") (pintype "bidirectional"))
    )
    (net (code "54") (name "unconnected-(K1-DS2-Pad5)") (class "Default")
      (node (ref "K1") (pin "5") (pinfunction "DS2_5") (pintype "passive"))
    )
    (net (code "55") (name "unconnected-(K1-K-Pad1)") (class "Default")
      (node (ref "K1") (pin "1") (pinfunction "K_1") (pintype "passive"))
    )
    (net (code "56") (name "unconnected-(U1-IO1-Pad9)") (class "Default")
      (node (ref "U1") (pin "9") (pinfunction "IO1_9") (pintype "bidirectional"))
    )
    (net (code "57") (name "unconnected-(U1-IO4-Pad4)") (class "Default")
      (node (ref "U1") (pin "4") (pinfunction "IO4_4") (pintype "bidirectional"))
    )
    (net (code "58") (name "unconnected-(U1-IO5-Pad5)") (class "Default")
      (node (ref "U1") (pin "5") (pinfunction "IO5_5") (pintype "bidirectional"))
    )
    (net (code "59") (name "unconnected-(U1-NC-Pad22)") (class "Default")
      (node (ref "U1") (pin "22") (pinfunction "NC_22") (pintype "no_connect"))
    )
  )
)
